# Power.net
KiCad netlist of a schematic drawn in Altium Designer
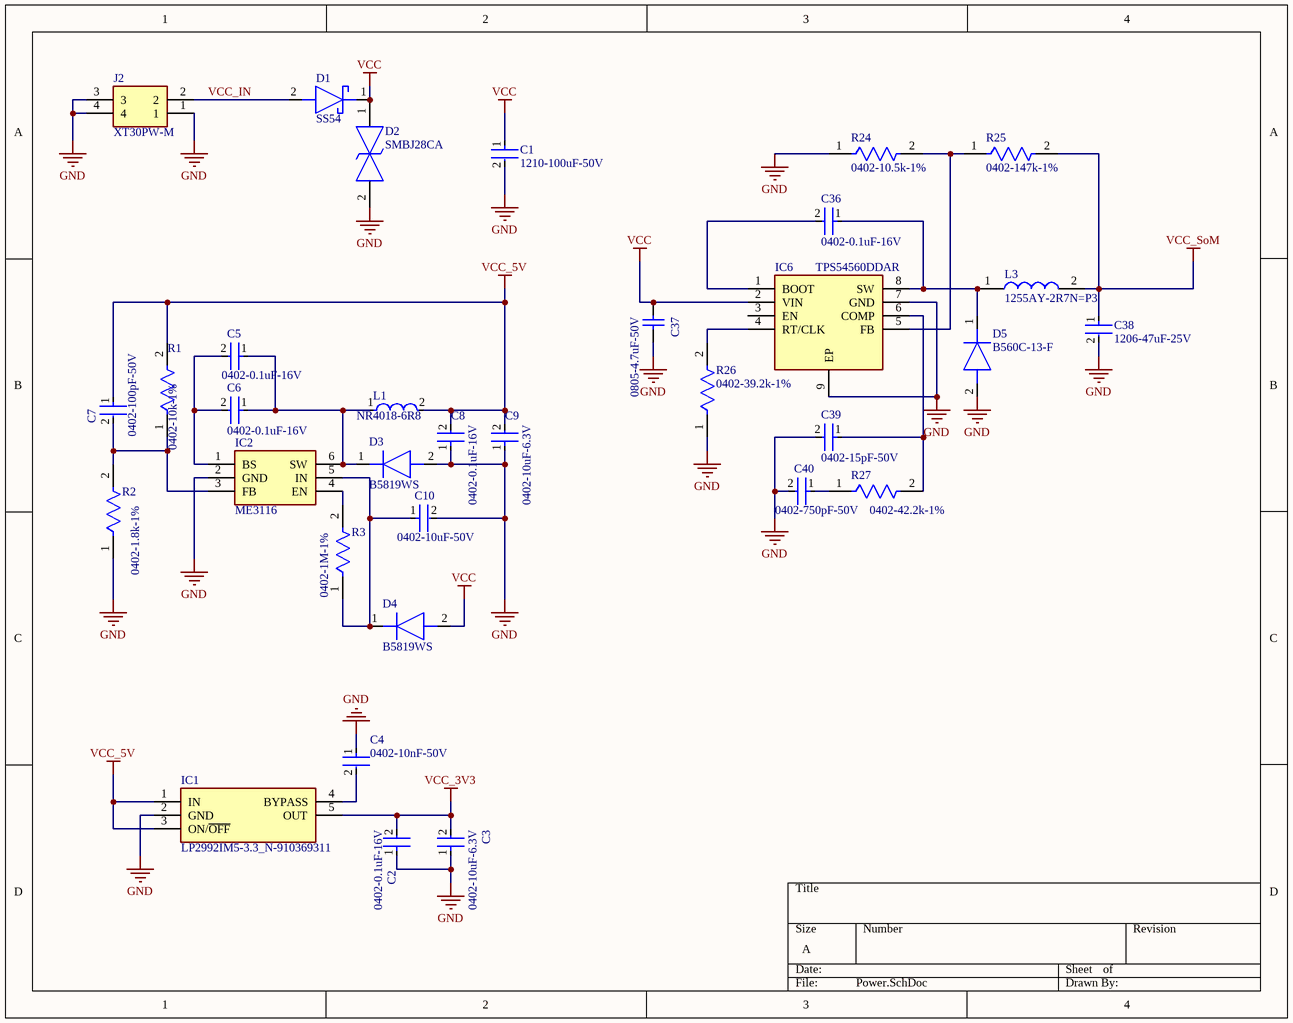
[diagram p0: Power.SchDoc]

(export (version "E")
  (design (tool "Eeschema 10.0.6"))
  (components
    (comp (ref "C1")
      (value "1210-100uF-50V")
      (footprint "FP-1210-L_3_3_0_4-W_2_5_0-IPC_B")
      (description "General Purpose Ceramic Capacitor, 1210, 22uF, 10%, X7R, 15%, 16V")
      (fields (field (name "VOLTAGE") "10V") (field (name "TOLERANCE") "10%"))
      (libsource (lib "Altium Content Vault") (part "b4654b650e69147ec39a6b967a45e02"))
    )
    (comp (ref "C2")
      (value "0402-0.1uF-16V")
      (footprint "FP-GRM155-0_05-IPC_A")
      (description "CAP CER 0.22UF 10V X5R 0402")
      (fields (field (name "VOLTAGE") "10V") (field (name "TOLERANCE") "10%"))
      (libsource (lib "Altium Content Vault") (part "02cd4be3c70576c341d710602a673aa"))
    )
    (comp (ref "C3")
      (value "0402-10uF-6.3V")
      (footprint "FP-GRM155-0_05-IPC_A")
      (description "CAP CER 0.22UF 10V X5R 0402")
      (fields (field (name "VOLTAGE") "10V") (field (name "TOLERANCE") "10%"))
      (libsource (lib "Altium Content Vault") (part "02cd4be3c70576c341d710602a673aa"))
    )
    (comp (ref "C4")
      (value "0402-10nF-50V")
      (footprint "FP-GRM155-0_05-IPC_A")
      (description "CAP CER 0.22UF 10V X5R 0402")
      (fields (field (name "VOLTAGE") "10V") (field (name "TOLERANCE") "10%"))
      (libsource (lib "Altium Content Vault") (part "02cd4be3c70576c341d710602a673aa"))
    )
    (comp (ref "C5")
      (value "0402-0.1uF-16V")
      (footprint "FP-GRM155-0_05-IPC_A")
      (description "CAP CER 0.22UF 10V X5R 0402")
      (fields (field (name "VOLTAGE") "10V") (field (name "TOLERANCE") "10%"))
      (libsource (lib "Altium Content Vault") (part "02cd4be3c70576c341d710602a673aa"))
    )
    (comp (ref "C6")
      (value "0402-0.1uF-16V")
      (footprint "FP-GRM155-0_05-IPC_A")
      (description "CAP CER 0.22UF 10V X5R 0402")
      (fields (field (name "VOLTAGE") "10V") (field (name "TOLERANCE") "10%"))
      (libsource (lib "Altium Content Vault") (part "02cd4be3c70576c341d710602a673aa"))
    )
    (comp (ref "C7")
      (value "0402-100pF-50V")
      (footprint "FP-GRM155-0_05-IPC_A")
      (description "CAP CER 0.22UF 10V X5R 0402")
      (fields (field (name "VOLTAGE") "10V") (field (name "TOLERANCE") "10%"))
      (libsource (lib "Altium Content Vault") (part "02cd4be3c70576c341d710602a673aa"))
    )
    (comp (ref "C8")
      (value "0402-0.1uF-16V")
      (footprint "FP-GRM155-0_05-IPC_A")
      (description "CAP CER 0.22UF 10V X5R 0402")
      (fields (field (name "VOLTAGE") "10V") (field (name "TOLERANCE") "10%"))
      (libsource (lib "Altium Content Vault") (part "02cd4be3c70576c341d710602a673aa"))
    )
    (comp (ref "C9")
      (value "0402-10uF-6.3V")
      (footprint "FP-GRM155-0_05-IPC_A")
      (description "CAP CER 0.22UF 10V X5R 0402")
      (fields (field (name "VOLTAGE") "10V") (field (name "TOLERANCE") "10%"))
      (libsource (lib "Altium Content Vault") (part "02cd4be3c70576c341d710602a673aa"))
    )
    (comp (ref "C10")
      (value "0402-10uF-50V")
      (footprint "FP-GRM155-0_05-IPC_A")
      (description "CAP CER 0.22UF 10V X5R 0402")
      (fields (field (name "VOLTAGE") "10V") (field (name "TOLERANCE") "10%"))
      (libsource (lib "Altium Content Vault") (part "02cd4be3c70576c341d710602a673aa"))
    )
    (comp (ref "C36")
      (value "0402-0.1uF-16V")
      (footprint "FP-GRM155-0_05-IPC_A")
      (description "CAP CER 0.22UF 10V X5R 0402")
      (fields (field (name "VOLTAGE") "10V") (field (name "TOLERANCE") "10%"))
      (libsource (lib "Altium Content Vault") (part "02cd4be3c70576c341d710602a673aa"))
    )
    (comp (ref "C37")
      (value "0805-4.7uF-50V")
      (footprint "CAPC2013X88X50LL20T25")
      (fields (field (name "MANUFACTURER") "Kemet") (field (name "PART NUMBER") "C0805C103K5RACTU"))
      (libsource (lib "Altium Content Vault") (part "CAP"))
    )
    (comp (ref "C38")
      (value "1206-47uF-25V")
      (footprint "FP-C3216-160-0_3-IPC_C")
      (description "Multilayer Ceramic Capacitors 100uF ±20% 10V X5R SMD 1206")
      (fields (field (name "VOLTAGE") "10V") (field (name "TOLERANCE") "20%"))
      (libsource (lib "Altium Content Vault") (part "02cd4be3c70576c341d710602a673aa"))
    )
    (comp (ref "C39")
      (value "0402-15pF-50V")
      (footprint "FP-GRM155-0_05-IPC_A")
      (description "CAP CER 0.22UF 10V X5R 0402")
      (fields (field (name "VOLTAGE") "10V") (field (name "TOLERANCE") "10%"))
      (libsource (lib "Altium Content Vault") (part "02cd4be3c70576c341d710602a673aa"))
    )
    (comp (ref "C40")
      (value "0402-750pF-50V")
      (footprint "FP-GRM155-0_05-IPC_A")
      (description "CAP CER 0.22UF 10V X5R 0402")
      (fields (field (name "VOLTAGE") "10V") (field (name "TOLERANCE") "10%"))
      (libsource (lib "Altium Content Vault") (part "02cd4be3c70576c341d710602a673aa"))
    )
    (comp (ref "D1")
      (value "SS54")
      (footprint "SamacSys:DIOM5026X262N")
      (description "Schottky Diode")
      (libsource (lib "SamacSys") (part "SS54"))
    )
    (comp (ref "D2")
      (value "SMBJ28CA")
      (footprint "SamacSys:DIONM5436X244N")
      (description "TVS Diode (Bi-directional)")
      (fields (field (name "MOUSER PART NUMBER") "652-SMBJ28CA"))
      (libsource (lib "*") (part "SMBJ28CA"))
    )
    (comp (ref "D3")
      (value "B5819WS")
      (footprint "SamacSys:SOD2613X100N")
      (description "Diode")
      (libsource (lib "*") (part "B5819WS"))
    )
    (comp (ref "D4")
      (value "B5819WS")
      (footprint "SamacSys:SOD2613X100N")
      (description "Diode")
      (libsource (lib "*") (part "B5819WS"))
    )
    (comp (ref "D5")
      (value "B560C-13-F")
      (footprint "SamacSys:DIOM7959X250N")
      (description "Diode")
      (fields (field (name "MOUSER PART NUMBER") "621-B560C-F"))
      (libsource (lib "*") (part "B560C-13-F"))
    )
    (comp (ref "IC1")
      (value "LP2992IM5-3.3_N-910369311")
      (footprint "SamacSys:SOT95P280X145-5N")
      (description "Integrated Circuit")
      (fields (field (name "MANUFACTURER_PART_NUMBER") "LP2992IM5-3.3/N-910369311"))
      (libsource (lib "*") (part "LP2992IM5-3.3_N-910369311"))
    )
    (comp (ref "IC2")
      (value "ME3116")
      (footprint "SamacSys:SOT95P270X145-6N")
      (description "Integrated Circuit")
      (libsource (lib "*") (part "ME3116"))
    )
    (comp (ref "IC6")
      (value "TPS54560DDAR")
      (footprint "SamacSys:SOIC127P600X170-9N")
      (description "Integrated Circuit")
      (fields (field (name "MOUSER PART NUMBER") "595-TPS54560DDAR"))
      (libsource (lib "*") (part "TPS54560DDAR"))
    )
    (comp (ref "J2")
      (value "XT30PW-M")
      (footprint "SamacSys:XT30PWM")
      (description "Connector")
      (libsource (lib "*") (part "XT30PW-M"))
    )
    (comp (ref "L1")
      (value "NR4018-6R8")
      (footprint "FP-NR4018-MFG")
      (description "SMD Power Inductors 2.2uH ±20% 1.44A 72mΩ")
      (fields (field (name "TOLERANCE") "20%"))
      (libsource (lib "Altium Content Vault") (part "725321dda6339637d4d059423bc1c3c"))
    )
    (comp (ref "L3")
      (value "1255AY-2R7N=P3")
      (footprint "SamacSys:1255AY100MP3")
      (description "Inductor")
      (fields (field (name "MOUSER PART NUMBER") "81-1255AY-2R7NP3"))
      (libsource (lib "*") (part "1255AY-2R7N=P3"))
    )
    (comp (ref "R1")
      (value "0402-10k-1%")
      (footprint "FP-CRCW0402-e3-IPC_C")
      (description "RES Thick Film, 0Ω, 0.063W, 0402")
      (fields (field (name "TOLERANCE") "5%"))
      (libsource (lib "Altium Content Vault") (part "1029c3af85768c4190bb7ad29bc67b5"))
    )
    (comp (ref "R2")
      (value "0402-1.8k-1%")
      (footprint "FP-CRCW0402-e3-IPC_C")
      (description "RES Thick Film, 0Ω, 0.063W, 0402")
      (fields (field (name "TOLERANCE") "5%"))
      (libsource (lib "Altium Content Vault") (part "1029c3af85768c4190bb7ad29bc67b5"))
    )
    (comp (ref "R3")
      (value "0402-1M-1%")
      (footprint "FP-CRCW0402-e3-IPC_C")
      (description "RES Thick Film, 0Ω, 0.063W, 0402")
      (fields (field (name "TOLERANCE") "5%"))
      (libsource (lib "Altium Content Vault") (part "1029c3af85768c4190bb7ad29bc67b5"))
    )
    (comp (ref "R24")
      (value "0402-10.5k-1%")
      (footprint "FP-CRCW0402-e3-IPC_C")
      (description "RES Thick Film, 0Ω, 0.063W, 0402")
      (fields (field (name "TOLERANCE") "5%"))
      (libsource (lib "Altium Content Vault") (part "1029c3af85768c4190bb7ad29bc67b5"))
    )
    (comp (ref "R25")
      (value "0402-147k-1%")
      (footprint "FP-CRCW0402-e3-IPC_C")
      (description "RES Thick Film, 0Ω, 0.063W, 0402")
      (fields (field (name "TOLERANCE") "5%"))
      (libsource (lib "Altium Content Vault") (part "1029c3af85768c4190bb7ad29bc67b5"))
    )
    (comp (ref "R26")
      (value "0402-39.2k-1%")
      (footprint "FP-CRCW0402-e3-IPC_C")
      (description "RES Thick Film, 0Ω, 0.063W, 0402")
      (fields (field (name "TOLERANCE") "5%"))
      (libsource (lib "Altium Content Vault") (part "1029c3af85768c4190bb7ad29bc67b5"))
    )
    (comp (ref "R27")
      (value "0402-42.2k-1%")
      (footprint "FP-CRCW0402-e3-IPC_C")
      (description "RES Thick Film, 0Ω, 0.063W, 0402")
      (fields (field (name "TOLERANCE") "5%"))
      (libsource (lib "Altium Content Vault") (part "1029c3af85768c4190bb7ad29bc67b5"))
    )
  )
  (nets
    (net (code "1") (name "/VCC_IN") (class "Default")
      (node (ref "D1") (pin "2") (pinfunction "A_2") (pintype "passive"))
      (node (ref "J2") (pin "2") (pinfunction "2_2") (pintype "passive"))
    )
    (net (code "2") (name "GND") (class "Default")
      (node (ref "C1") (pin "2") (pinfunction "2_2") (pintype "passive"))
      (node (ref "C10") (pin "2") (pinfunction "2_2") (pintype "passive"))
      (node (ref "C2") (pin "1") (pinfunction "1_1") (pintype "passive"))
      (node (ref "C3") (pin "1") (pinfunction "1_1") (pintype "passive"))
      (node (ref "C37") (pin "1") (pinfunction "1_1") (pintype "passive"))
      (node (ref "C38") (pin "2") (pinfunction "2_2") (pintype "passive"))
      (node (ref "C39") (pin "2") (pinfunction "2_2") (pintype "passive"))
      (node (ref "C4") (pin "1") (pinfunction "1_1") (pintype "passive"))
      (node (ref "C40") (pin "2") (pinfunction "2_2") (pintype "passive"))
      (node (ref "C8") (pin "1") (pinfunction "1_1") (pintype "passive"))
      (node (ref "C9") (pin "1") (pinfunction "1_1") (pintype "passive"))
      (node (ref "D2") (pin "2") (pinfunction "2_2") (pintype "passive"))
      (node (ref "D3") (pin "2") (pinfunction "A_2") (pintype "power_in"))
      (node (ref "D5") (pin "2") (pinfunction "A_2") (pintype "passive"))
      (node (ref "IC1") (pin "2") (pinfunction "GND_2") (pintype "passive"))
      (node (ref "IC2") (pin "2") (pinfunction "GND_2") (pintype "passive"))
      (node (ref "IC6") (pin "7") (pinfunction "GND_7") (pintype "passive"))
      (node (ref "IC6") (pin "9") (pinfunction "EP_9") (pintype "passive"))
      (node (ref "J2") (pin "1") (pinfunction "1_1") (pintype "passive"))
      (node (ref "J2") (pin "3") (pinfunction "3_3") (pintype "passive"))
      (node (ref "J2") (pin "4") (pinfunction "4_4") (pintype "passive"))
      (node (ref "R2") (pin "1") (pinfunction "1_1") (pintype "passive"))
      (node (ref "R24") (pin "1") (pinfunction "1_1") (pintype "passive"))
      (node (ref "R26") (pin "1") (pinfunction "1_1") (pintype "passive"))
    )
    (net (code "3") (name "Net-(C40-Pad1)") (class "Default")
      (node (ref "C40") (pin "1") (pinfunction "1_1") (pintype "passive"))
      (node (ref "R27") (pin "1") (pinfunction "1_1") (pintype "passive"))
    )
    (net (code "4") (name "Net-(D3-K)") (class "Default")
      (node (ref "C5") (pin "1") (pinfunction "1_1") (pintype "passive"))
      (node (ref "C6") (pin "1") (pinfunction "1_1") (pintype "passive"))
      (node (ref "D3") (pin "1") (pinfunction "K_1") (pintype "power_in"))
      (node (ref "IC2") (pin "6") (pinfunction "SW_6") (pintype "passive"))
      (node (ref "L1") (pin "1") (pinfunction "1_1") (pintype "passive"))
    )
    (net (code "5") (name "Net-(D4-K)") (class "Default")
      (node (ref "C10") (pin "1") (pinfunction "1_1") (pintype "passive"))
      (node (ref "D4") (pin "1") (pinfunction "K_1") (pintype "power_in"))
      (node (ref "IC2") (pin "5") (pinfunction "IN_5") (pintype "passive"))
      (node (ref "R3") (pin "1") (pinfunction "1_1") (pintype "passive"))
    )
    (net (code "6") (name "Net-(D5-K)") (class "Default")
      (node (ref "C36") (pin "1") (pinfunction "1_1") (pintype "passive"))
      (node (ref "D5") (pin "1") (pinfunction "K_1") (pintype "passive"))
      (node (ref "IC6") (pin "8") (pinfunction "SW_8") (pintype "passive"))
      (node (ref "L3") (pin "1") (pinfunction "1_1") (pintype "passive"))
    )
    (net (code "7") (name "Net-(IC1-BYPASS)") (class "Default")
      (node (ref "C4") (pin "2") (pinfunction "2_2") (pintype "passive"))
      (node (ref "IC1") (pin "4") (pinfunction "BYPASS_4") (pintype "passive"))
    )
    (net (code "8") (name "Net-(IC2-BS)") (class "Default")
      (node (ref "C5") (pin "2") (pinfunction "2_2") (pintype "passive"))
      (node (ref "C6") (pin "2") (pinfunction "2_2") (pintype "passive"))
      (node (ref "IC2") (pin "1") (pinfunction "BS_1") (pintype "passive"))
    )
    (net (code "9") (name "Net-(IC2-EN)") (class "Default")
      (node (ref "IC2") (pin "4") (pinfunction "EN_4") (pintype "passive"))
      (node (ref "R3") (pin "2") (pinfunction "2_2") (pintype "passive"))
    )
    (net (code "10") (name "Net-(IC2-FB)") (class "Default")
      (node (ref "C7") (pin "2") (pinfunction "2_2") (pintype "passive"))
      (node (ref "IC2") (pin "3") (pinfunction "FB_3") (pintype "passive"))
      (node (ref "R1") (pin "1") (pinfunction "1_1") (pintype "passive"))
      (node (ref "R2") (pin "2") (pinfunction "2_2") (pintype "passive"))
    )
    (net (code "11") (name "Net-(IC6-BOOT)") (class "Default")
      (node (ref "C36") (pin "2") (pinfunction "2_2") (pintype "passive"))
      (node (ref "IC6") (pin "1") (pinfunction "BOOT_1") (pintype "passive"))
    )
    (net (code "12") (name "Net-(IC6-COMP)") (class "Default")
      (node (ref "C39") (pin "1") (pinfunction "1_1") (pintype "passive"))
      (node (ref "IC6") (pin "6") (pinfunction "COMP_6") (pintype "passive"))
      (node (ref "R27") (pin "2") (pinfunction "2_2") (pintype "passive"))
    )
    (net (code "13") (name "Net-(IC6-FB)") (class "Default")
      (node (ref "IC6") (pin "5") (pinfunction "FB_5") (pintype "passive"))
      (node (ref "R24") (pin "2") (pinfunction "2_2") (pintype "passive"))
      (node (ref "R25") (pin "1") (pinfunction "1_1") (pintype "passive"))
    )
    (net (code "14") (name "Net-(IC6-RT{slash}CLK)") (class "Default")
      (node (ref "IC6") (pin "4") (pinfunction "RT/CLK_4") (pintype "passive"))
      (node (ref "R26") (pin "2") (pinfunction "2_2") (pintype "passive"))
    )
    (net (code "15") (name "VCC") (class "Default")
      (node (ref "C1") (pin "1") (pinfunction "1_1") (pintype "passive"))
      (node (ref "C37") (pin "2") (pinfunction "2_2") (pintype "passive"))
      (node (ref "D1") (pin "1") (pinfunction "K_1") (pintype "passive"))
      (node (ref "D2") (pin "1") (pinfunction "1_1") (pintype "passive"))
      (node (ref "D4") (pin "2") (pinfunction "A_2") (pintype "power_in"))
      (node (ref "IC6") (pin "2") (pinfunction "VIN_2") (pintype "passive"))
    )
    (net (code "16") (name "VCC_3V3") (class "Default")
      (node (ref "C2") (pin "2") (pinfunction "2_2") (pintype "passive"))
      (node (ref "C3") (pin "2") (pinfunction "2_2") (pintype "passive"))
      (node (ref "IC1") (pin "5") (pinfunction "OUT_5") (pintype "passive"))
    )
    (net (code "17") (name "VCC_5V") (class "Default")
      (node (ref "C7") (pin "1") (pinfunction "1_1") (pintype "passive"))
      (node (ref "C8") (pin "2") (pinfunction "2_2") (pintype "passive"))
      (node (ref "C9") (pin "2") (pinfunction "2_2") (pintype "passive"))
      (node (ref "IC1") (pin "1") (pinfunction "IN_1") (pintype "passive"))
      (node (ref "IC1") (pin "3") (pinfunction "ON/~{OFF}_3") (pintype "passive"))
      (node (ref "L1") (pin "2") (pinfunction "2_2") (pintype "passive"))
      (node (ref "R1") (pin "2") (pinfunction "2_2") (pintype "passive"))
    )
    (net (code "18") (name "VCC_SoM") (class "Default")
      (node (ref "C38") (pin "1") (pinfunction "1_1") (pintype "passive"))
      (node (ref "L3") (pin "2") (pinfunction "2_2") (pintype "passive"))
      (node (ref "R25") (pin "2") (pinfunction "2_2") (pintype "passive"))
    )
    (net (code "19") (name "unconnected-(IC6-EN-Pad3)") (class "Default")
      (node (ref "IC6") (pin "3") (pinfunction "EN_3") (pintype "passive"))
    )
  )
)
